# PageMain.net
KiCad netlist of a schematic drawn in Altium Designer
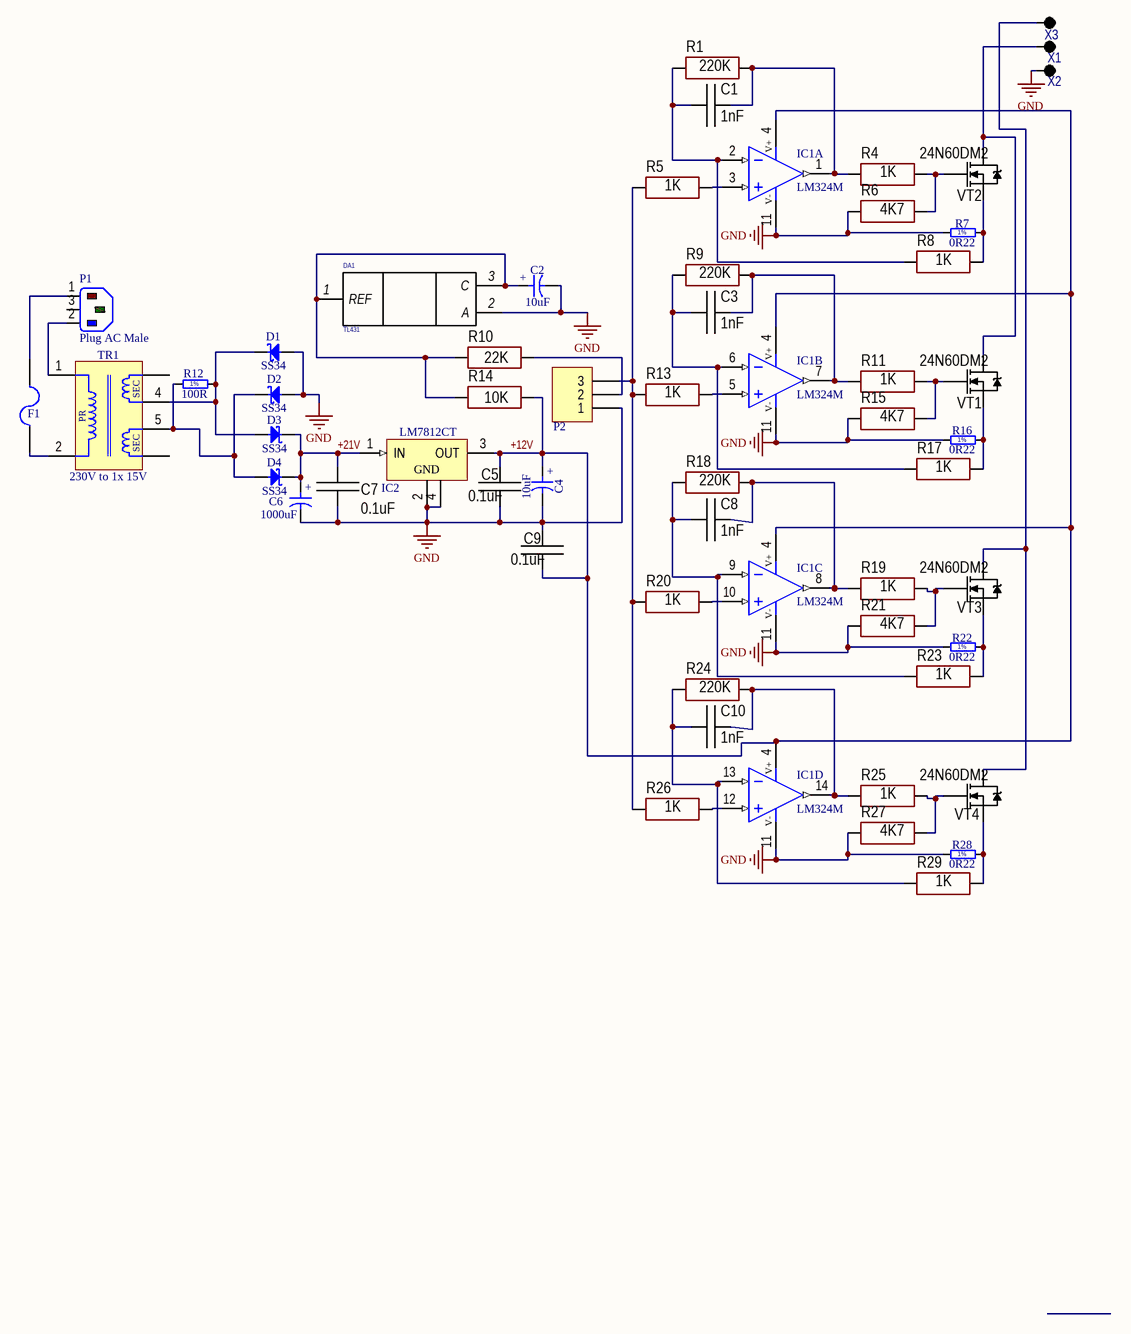
[diagram p0: PageMain.SchDoc]

(export (version "E")
  (design (tool "Eeschema 10.0.6"))
  (components
    (comp (ref "C1")
      (value "1nF")
      (footprint "CAP: 0805")
      (fields
        (field (name "MANUFACTURER") "Yageo")
        (field (name "PARTNUMBER") "CC0805KRX7R7BB104")
        (field (name "VALUEMANUFACTURERPARTNUMBER") "Ceramic capacitor, 1nF, X7R, ±10%, 16V, 0805, -55...+125°C")
      )
      (libsource (lib "Capacitor") (part "Ceramic_0805"))
    )
    (comp (ref "C2")
      (value "10uF")
      (footprint "CAPPR200-500X1100")
      (description "Polarised capacitor")
      (fields
        (field (name "PART NUMBER") "CAER_10UF_63V_20%_PANASONIC_ECA1JM100")
        (field (name "VOLTAGE") "63V")
        (field (name "AUTHOR") "CERN DEM JLC")
      )
      (libsource (lib "Capacitors") (part "Capacitor - polarized"))
    )
    (comp (ref "C3")
      (value "1nF")
      (footprint "CAP: 0805")
      (fields
        (field (name "MANUFACTURER") "Yageo")
        (field (name "PARTNUMBER") "CC0805KRX7R7BB104")
        (field (name "VALUEMANUFACTURERPARTNUMBER") "Ceramic capacitor, 1nF, X7R, ±10%, 16V, 0805, -55...+125°C")
      )
      (libsource (lib "Capacitor") (part "Ceramic_0805"))
    )
    (comp (ref "C4")
      (value "10uF")
      (footprint "CAPPR200-500X1100")
      (description "Polarised capacitor")
      (fields
        (field (name "PART NUMBER") "CAER_10UF_63V_20%_PANASONIC_ECA1JM100")
        (field (name "VOLTAGE") "63V")
        (field (name "AUTHOR") "CERN DEM JLC")
      )
      (libsource (lib "Capacitors") (part "Capacitor - polarized"))
    )
    (comp (ref "C5")
      (value "0.1uF")
      (footprint "CAP: 0805")
      (fields
        (field (name "MANUFACTURER") "Yageo")
        (field (name "PARTNUMBER") "CC0805KRX7R7BB104")
        (field (name "VALUEMANUFACTURERPARTNUMBER") "Ceramic capacitor, 0.1uF, X7R, ±10%, 16V, 0805, -55...+125°C")
      )
      (libsource (lib "Capacitor") (part "Ceramic_0805"))
    )
    (comp (ref "C6")
      (value "1000uF")
      (footprint "CAPPR500-1300X2700")
      (description "Polarised capacitor")
      (fields
        (field (name "PART NUMBER") "CAER_1000UF_35V_20%_VISHAY_MAL215050102E3")
        (field (name "VOLTAGE") "35V")
        (field (name "AUTHOR") "CERN DEM JLC")
      )
      (libsource (lib "Capacitors") (part "Capacitor - polarized"))
    )
    (comp (ref "C7")
      (value "0.1uF")
      (footprint "CAP: 0805")
      (fields
        (field (name "MANUFACTURER") "Yageo")
        (field (name "PARTNUMBER") "CC0805KRX7R7BB104")
        (field (name "VALUEMANUFACTURERPARTNUMBER") "Ceramic capacitor, 0.1uF, X7R, ±10%, 16V, 0805, -55...+125°C")
      )
      (libsource (lib "Capacitor") (part "Ceramic_0805"))
    )
    (comp (ref "C8")
      (value "1nF")
      (footprint "CAP: 0805")
      (fields
        (field (name "MANUFACTURER") "Yageo")
        (field (name "PARTNUMBER") "CC0805KRX7R7BB104")
        (field (name "VALUEMANUFACTURERPARTNUMBER") "Ceramic capacitor, 1nF, X7R, ±10%, 16V, 0805, -55...+125°C")
      )
      (libsource (lib "Capacitor") (part "Ceramic_0805"))
    )
    (comp (ref "C9")
      (value "0.1uF")
      (footprint "CAP: 0805")
      (fields
        (field (name "MANUFACTURER") "Yageo")
        (field (name "PARTNUMBER") "CC0805KRX7R7BB104")
        (field (name "VALUEMANUFACTURERPARTNUMBER") "Ceramic capacitor, 0.1uF, X7R, ±10%, 16V, 0805, -55...+125°C")
      )
      (libsource (lib "Capacitor") (part "Ceramic_0805"))
    )
    (comp (ref "C10")
      (value "1nF")
      (footprint "CAP: 0805")
      (fields
        (field (name "MANUFACTURER") "Yageo")
        (field (name "PARTNUMBER") "CC0805KRX7R7BB104")
        (field (name "VALUEMANUFACTURERPARTNUMBER") "Ceramic capacitor, 1nF, X7R, ±10%, 16V, 0805, -55...+125°C")
      )
      (libsource (lib "Capacitor") (part "Ceramic_0805"))
    )
    (comp (ref "D1")
      (value "SS34")
      (footprint "DIOM7659X265N")
      (description "Schottky Diode")
      (fields
        (field (name "VOLTAGE") "40V")
        (field (name "POWER") "3A")
        (field (name "AUTHOR") "CERN DEM JLC")
      )
      (libsource (lib "ICs And Semiconductors") (part "Diode Schottky"))
    )
    (comp (ref "D2")
      (value "SS34")
      (footprint "DIOM7659X265N")
      (description "Schottky Diode")
      (fields
        (field (name "VOLTAGE") "40V")
        (field (name "POWER") "3A")
        (field (name "AUTHOR") "CERN DEM JLC")
      )
      (libsource (lib "ICs And Semiconductors") (part "Diode Schottky"))
    )
    (comp (ref "D3")
      (value "SS34")
      (footprint "DIOM7659X265N")
      (description "Schottky Diode")
      (fields
        (field (name "VOLTAGE") "40V")
        (field (name "POWER") "3A")
        (field (name "AUTHOR") "CERN DEM JLC")
      )
      (libsource (lib "ICs And Semiconductors") (part "Diode Schottky"))
    )
    (comp (ref "D4")
      (value "SS34")
      (footprint "DIOM7659X265N")
      (description "Schottky Diode")
      (fields
        (field (name "VOLTAGE") "40V")
        (field (name "POWER") "3A")
        (field (name "AUTHOR") "CERN DEM JLC")
      )
      (libsource (lib "ICs And Semiconductors") (part "Diode Schottky"))
    )
    (comp (ref "DA1") (value "TL431") (footprint "TO-92") (libsource (lib "lib") (part "TL431")))
    (comp (ref "F1")
      (value "~")
      (footprint "PIN-W2/E2.8")
      (description "Fuse")
      (fields (field (name "PUBLISHER") "Altium Limited"))
      (libsource (lib "Miscellaneous Devices") (part "Fuse 2"))
    )
    (comp (ref "IC1")
      (value "LM324M")
      (footprint "SOIC127P600X175-14N")
      (description "Quad Operational Amplifier")
      (fields (field (name "MANUFACTURER") "FAIRCHILD SEMICONDUCTOR") (field (name "AUTHOR") "CERN DEM JLC"))
      (libsource (lib "ICs And Semiconductors") (part "Operational Amplifier x4 Type1"))
    )
    (comp (ref "IC2")
      (value "LM7812CT")
      (footprint "TO-220-H")
      (description "3-Terminal Regulator 1=IN 2=GND 3=OUT 4=GND")
      (fields
        (field (name "PART NUMBER") "LM7812CT_h")
        (field (name "MANUFACTURER") "FAIRCHILD SEMICONDUCTOR")
        (field (name "AUTHOR") "CERN DEM JLC")
      )
      (libsource (lib "ICs And Semiconductors") (part "REG3+1 1IN-2GND-3OUT+4GND"))
    )
    (comp (ref "P1")
      (value "Plug AC Male")
      (footprint "IEC9.14-2H3")
      (description "IEC Mains Power Inlet, EN60 320-1 C14 Class I Cold Condition, PC Flange Rear Mount, Chassis Plug")
      (fields (field (name "PUBLISHER") "Altium Limited"))
      (libsource (lib "Miscellaneous Connectors") (part "Plug AC Male"))
    )
    (comp (ref "P2")
      (value "Header 3")
      (footprint "HDR1X3")
      (description "Header, 3-Pin")
      (fields (field (name "PUBLISHER") "Altium Limited"))
      (libsource (lib "Miscellaneous Connectors") (part "Header 3"))
    )
    (comp (ref "R1")
      (value "220K")
      (footprint "RES: 0805")
      (fields
        (field (name "MANUFACTURER") "Yageo")
        (field (name "PARTNUMBER") "RC0805JR-07100RL")
        (field (name "VALUEMANUFACTURERPARTNUMBER") "Resistor film, 220K, ±5%, 0805, 0.125W, -55...+125°C")
      )
      (libsource (lib "") (part "Resistor_0805_1"))
    )
    (comp (ref "R4")
      (value "1K")
      (footprint "RES: 0805")
      (fields
        (field (name "MANUFACTURER") "Yageo")
        (field (name "PARTNUMBER") "RC0805JR-07100RL")
        (field (name "VALUEMANUFACTURERPARTNUMBER") "Resistor film, 1K, ±5%, 0805, 0.125W, -55...+125°C")
      )
      (libsource (lib "Resistor") (part "Resistor_0805"))
    )
    (comp (ref "R5")
      (value "1K")
      (footprint "RES: 0805")
      (fields
        (field (name "MANUFACTURER") "Yageo")
        (field (name "PARTNUMBER") "RC0805JR-07100RL")
        (field (name "VALUEMANUFACTURERPARTNUMBER") "Resistor film, 1K, ±5%, 0805, 0.125W, -55...+125°C")
      )
      (libsource (lib "") (part "Resistor_0805_1"))
    )
    (comp (ref "R6")
      (value "4K7")
      (footprint "RES: 0805")
      (fields
        (field (name "MANUFACTURER") "Yageo")
        (field (name "PARTNUMBER") "RC0805JR-07100RL")
        (field (name "VALUEMANUFACTURERPARTNUMBER") "Resistor film, 4K7, ±5%, 0805, 0.125W, -55...+125°C")
      )
      (libsource (lib "Resistor") (part "Resistor_0805"))
    )
    (comp (ref "R7")
      (value "0R22")
      (footprint "RES_OHMITE_45")
      (description "Resistor")
      (fields (field (name "POWER") "5W") (field (name "AUTHOR") "CERN DEM MR"))
      (libsource (lib "Resistors") (part "Resistor - 1%"))
    )
    (comp (ref "R8")
      (value "1K")
      (footprint "RES: 0805")
      (fields
        (field (name "MANUFACTURER") "Yageo")
        (field (name "PARTNUMBER") "RC0805JR-07100RL")
        (field (name "VALUEMANUFACTURERPARTNUMBER") "Resistor film, 1K, ±5%, 0805, 0.125W, -55...+125°C")
      )
      (libsource (lib "") (part "Resistor_0805_1"))
    )
    (comp (ref "R9")
      (value "220K")
      (footprint "RES: 0805")
      (fields
        (field (name "MANUFACTURER") "Yageo")
        (field (name "PARTNUMBER") "RC0805JR-07100RL")
        (field (name "VALUEMANUFACTURERPARTNUMBER") "Resistor film, 220K, ±5%, 0805, 0.125W, -55...+125°C")
      )
      (libsource (lib "") (part "Resistor_0805_1"))
    )
    (comp (ref "R10")
      (value "22K")
      (footprint "RES: 0805")
      (fields
        (field (name "MANUFACTURER") "Yageo")
        (field (name "PARTNUMBER") "RC0805JR-07100RL")
        (field (name "VALUEMANUFACTURERPARTNUMBER") "Resistor film, 22K, ±5%, 0805, 0.125W, -55...+125°C")
      )
      (libsource (lib "") (part "Resistor_0805_2"))
    )
    (comp (ref "R11")
      (value "1K")
      (footprint "RES: 0805")
      (fields
        (field (name "MANUFACTURER") "Yageo")
        (field (name "PARTNUMBER") "RC0805JR-07100RL")
        (field (name "VALUEMANUFACTURERPARTNUMBER") "Resistor film, 1K, ±5%, 0805, 0.125W, -55...+125°C")
      )
      (libsource (lib "Resistor") (part "Resistor_0805"))
    )
    (comp (ref "R12")
      (value "100R")
      (footprint "RES_OHMITE_45")
      (description "Resistor")
      (fields (field (name "POWER") "5W") (field (name "AUTHOR") "CERN DEM MR"))
      (libsource (lib "Resistors") (part "Resistor - 1%"))
    )
    (comp (ref "R13")
      (value "1K")
      (footprint "RES: 0805")
      (fields
        (field (name "MANUFACTURER") "Yageo")
        (field (name "PARTNUMBER") "RC0805JR-07100RL")
        (field (name "VALUEMANUFACTURERPARTNUMBER") "Resistor film, 1K, ±5%, 0805, 0.125W, -55...+125°C")
      )
      (libsource (lib "") (part "Resistor_0805_1"))
    )
    (comp (ref "R14")
      (value "10K")
      (footprint "RES: 0805")
      (fields
        (field (name "MANUFACTURER") "Yageo")
        (field (name "PARTNUMBER") "RC0805JR-07100RL")
        (field (name "VALUEMANUFACTURERPARTNUMBER") "Resistor film, 10K, ±5%, 0805, 0.125W, -55...+125°C")
      )
      (libsource (lib "") (part "Resistor_0805_2"))
    )
    (comp (ref "R15")
      (value "4K7")
      (footprint "RES: 0805")
      (fields
        (field (name "MANUFACTURER") "Yageo")
        (field (name "PARTNUMBER") "RC0805JR-07100RL")
        (field (name "VALUEMANUFACTURERPARTNUMBER") "Resistor film, 4K7, ±5%, 0805, 0.125W, -55...+125°C")
      )
      (libsource (lib "Resistor") (part "Resistor_0805"))
    )
    (comp (ref "R16")
      (value "0R22")
      (footprint "RES_OHMITE_45")
      (description "Resistor")
      (fields (field (name "POWER") "5W") (field (name "AUTHOR") "CERN DEM MR"))
      (libsource (lib "Resistors") (part "Resistor - 1%"))
    )
    (comp (ref "R17")
      (value "1K")
      (footprint "RES: 0805")
      (fields
        (field (name "MANUFACTURER") "Yageo")
        (field (name "PARTNUMBER") "RC0805JR-07100RL")
        (field (name "VALUEMANUFACTURERPARTNUMBER") "Resistor film, 1K, ±5%, 0805, 0.125W, -55...+125°C")
      )
      (libsource (lib "") (part "Resistor_0805_1"))
    )
    (comp (ref "R18")
      (value "220K")
      (footprint "RES: 0805")
      (fields
        (field (name "MANUFACTURER") "Yageo")
        (field (name "PARTNUMBER") "RC0805JR-07100RL")
        (field (name "VALUEMANUFACTURERPARTNUMBER") "Resistor film, 220K, ±5%, 0805, 0.125W, -55...+125°C")
      )
      (libsource (lib "") (part "Resistor_0805_1"))
    )
    (comp (ref "R19")
      (value "1K")
      (footprint "RES: 0805")
      (fields
        (field (name "MANUFACTURER") "Yageo")
        (field (name "PARTNUMBER") "RC0805JR-07100RL")
        (field (name "VALUEMANUFACTURERPARTNUMBER") "Resistor film, 1K, ±5%, 0805, 0.125W, -55...+125°C")
      )
      (libsource (lib "Resistor") (part "Resistor_0805"))
    )
    (comp (ref "R20")
      (value "1K")
      (footprint "RES: 0805")
      (fields
        (field (name "MANUFACTURER") "Yageo")
        (field (name "PARTNUMBER") "RC0805JR-07100RL")
        (field (name "VALUEMANUFACTURERPARTNUMBER") "Resistor film, 1K, ±5%, 0805, 0.125W, -55...+125°C")
      )
      (libsource (lib "") (part "Resistor_0805_1"))
    )
    (comp (ref "R21")
      (value "4K7")
      (footprint "RES: 0805")
      (fields
        (field (name "MANUFACTURER") "Yageo")
        (field (name "PARTNUMBER") "RC0805JR-07100RL")
        (field (name "VALUEMANUFACTURERPARTNUMBER") "Resistor film, 4K7, ±5%, 0805, 0.125W, -55...+125°C")
      )
      (libsource (lib "Resistor") (part "Resistor_0805"))
    )
    (comp (ref "R22")
      (value "0R22")
      (footprint "RES_OHMITE_45")
      (description "Resistor")
      (fields (field (name "POWER") "5W") (field (name "AUTHOR") "CERN DEM MR"))
      (libsource (lib "Resistors") (part "Resistor - 1%"))
    )
    (comp (ref "R23")
      (value "1K")
      (footprint "RES: 0805")
      (fields
        (field (name "MANUFACTURER") "Yageo")
        (field (name "PARTNUMBER") "RC0805JR-07100RL")
        (field (name "VALUEMANUFACTURERPARTNUMBER") "Resistor film, 1K, ±5%, 0805, 0.125W, -55...+125°C")
      )
      (libsource (lib "") (part "Resistor_0805_1"))
    )
    (comp (ref "R24")
      (value "220K")
      (footprint "RES: 0805")
      (fields
        (field (name "MANUFACTURER") "Yageo")
        (field (name "PARTNUMBER") "RC0805JR-07100RL")
        (field (name "VALUEMANUFACTURERPARTNUMBER") "Resistor film, 220K, ±5%, 0805, 0.125W, -55...+125°C")
      )
      (libsource (lib "") (part "Resistor_0805_1"))
    )
    (comp (ref "R25")
      (value "1K")
      (footprint "RES: 0805")
      (fields
        (field (name "MANUFACTURER") "Yageo")
        (field (name "PARTNUMBER") "RC0805JR-07100RL")
        (field (name "VALUEMANUFACTURERPARTNUMBER") "Resistor film, 1K, ±5%, 0805, 0.125W, -55...+125°C")
      )
      (libsource (lib "Resistor") (part "Resistor_0805"))
    )
    (comp (ref "R26")
      (value "1K")
      (footprint "RES: 0805")
      (fields
        (field (name "MANUFACTURER") "Yageo")
        (field (name "PARTNUMBER") "RC0805JR-07100RL")
        (field (name "VALUEMANUFACTURERPARTNUMBER") "Resistor film, 1K, ±5%, 0805, 0.125W, -55...+125°C")
      )
      (libsource (lib "") (part "Resistor_0805_1"))
    )
    (comp (ref "R27")
      (value "4K7")
      (footprint "RES: 0805")
      (fields
        (field (name "MANUFACTURER") "Yageo")
        (field (name "PARTNUMBER") "RC0805JR-07100RL")
        (field (name "VALUEMANUFACTURERPARTNUMBER") "Resistor film, 4K7, ±5%, 0805, 0.125W, -55...+125°C")
      )
      (libsource (lib "Resistor") (part "Resistor_0805"))
    )
    (comp (ref "R28")
      (value "0R22")
      (footprint "RES_OHMITE_45")
      (description "Resistor")
      (fields (field (name "POWER") "5W") (field (name "AUTHOR") "CERN DEM MR"))
      (libsource (lib "Resistors") (part "Resistor - 1%"))
    )
    (comp (ref "R29")
      (value "1K")
      (footprint "RES: 0805")
      (fields
        (field (name "MANUFACTURER") "Yageo")
        (field (name "PARTNUMBER") "RC0805JR-07100RL")
        (field (name "VALUEMANUFACTURERPARTNUMBER") "Resistor film, 1K, ±5%, 0805, 0.125W, -55...+125°C")
      )
      (libsource (lib "") (part "Resistor_0805_1"))
    )
    (comp (ref "TR1")
      (value "230V to 1x 15V")
      (footprint "XFMR_CLAIRTRONIC_14102")
      (description "Transformer 1xPrim 1xSec Type1")
      (fields
        (field (name "PART NUMBER") "XFMR_CLAIRTRONIC_14102")
        (field (name "MANUFACTURER") "CLAIRTRONIC LTD")
        (field (name "AUTHOR") "CERN DEM JMW")
      )
      (libsource (lib "Inductors & Transformers") (part "Transformer 1xPrim 2xSec Type1"))
    )
    (comp (ref "VT1")
      (value "~")
      (footprint "TO247")
      (fields
        (field (name "MANUFACTURER") "Infineon Technologies")
        (field (name "VALUEMANUFACTURERPARTNUMBER") "MOSFET N-channel transistor, 80V, 7A, 9.1nC, 2.5W, 34mOhm, 756pF, 8-TDSON, -55...+150°C")
        (field (name "PARTNUMBER") "24N60DM2")
      )
      (libsource (lib "Transistor") (part "MOSFET_N_123"))
    )
    (comp (ref "VT2")
      (value "~")
      (footprint "TO247")
      (fields
        (field (name "MANUFACTURER") "Infineon Technologies")
        (field (name "VALUEMANUFACTURERPARTNUMBER") "MOSFET N-channel transistor, 80V, 7A, 9.1nC, 2.5W, 34mOhm, 756pF, 8-TDSON, -55...+150°C")
        (field (name "PARTNUMBER") "24N60DM2")
      )
      (libsource (lib "Transistor") (part "MOSFET_N_123"))
    )
    (comp (ref "VT3")
      (value "~")
      (footprint "TO247")
      (fields
        (field (name "MANUFACTURER") "Infineon Technologies")
        (field (name "VALUEMANUFACTURERPARTNUMBER") "MOSFET N-channel transistor, 80V, 7A, 9.1nC, 2.5W, 34mOhm, 756pF, 8-TDSON, -55...+150°C")
        (field (name "PARTNUMBER") "24N60DM2")
      )
      (libsource (lib "Transistor") (part "MOSFET_N_123"))
    )
    (comp (ref "VT4")
      (value "~")
      (footprint "TO247")
      (fields
        (field (name "MANUFACTURER") "Infineon Technologies")
        (field (name "VALUEMANUFACTURERPARTNUMBER") "MOSFET N-channel transistor, 80V, 7A, 9.1nC, 2.5W, 34mOhm, 756pF, 8-TDSON, -55...+150°C")
        (field (name "PARTNUMBER") "24N60DM2")
      )
      (libsource (lib "Transistor") (part "MOSFET_N_123"))
    )
    (comp (ref "X1")
      (value "62650-1")
      (footprint "62650-1")
      (description "Ножевой контакт 6,3мм на плату")
      (fields (field (name "MANUFACTURER") "TE Connectivity"))
      (libsource (lib "lib") (part "POINT"))
    )
    (comp (ref "X2")
      (value "62650-1")
      (footprint "62650-1")
      (description "Ножевой контакт 6,3мм на плату")
      (fields (field (name "MANUFACTURER") "TE Connectivity"))
      (libsource (lib "lib") (part "POINT"))
    )
    (comp (ref "X3")
      (value "62650-1")
      (footprint "62650-1")
      (description "Ножевой контакт 6,3мм на плату")
      (fields (field (name "MANUFACTURER") "TE Connectivity"))
      (libsource (lib "lib") (part "POINT"))
    )
  )
  (nets
    (net (code "1") (name "/+12V") (class "Default")
      (node (ref "C4") (pin "1") (pinfunction "1_1") (pintype "passive"))
      (node (ref "C5") (pin "1") (pinfunction "1_1") (pintype "power_in"))
      (node (ref "C9") (pin "2") (pinfunction "2_2") (pintype "power_in"))
      (node (ref "IC1") (pin "4") (pinfunction "V+_4") (pintype "power_in"))
      (node (ref "IC2") (pin "3") (pinfunction "OUT_3") (pintype "power_in"))
      (node (ref "R14") (pin "1") (pinfunction "1_1") (pintype "passive"))
    )
    (net (code "2") (name "/+21V") (class "Default")
      (node (ref "C6") (pin "1") (pinfunction "1_1") (pintype "passive"))
      (node (ref "C7") (pin "1") (pinfunction "1_1") (pintype "power_in"))
      (node (ref "D3") (pin "1") (pinfunction "C_1") (pintype "passive"))
      (node (ref "D4") (pin "1") (pinfunction "C_1") (pintype "passive"))
      (node (ref "IC2") (pin "1") (pinfunction "IN_1") (pintype "input"))
    )
    (net (code "3") (name "GND") (class "Default")
      (node (ref "C2") (pin "2") (pinfunction "2_2") (pintype "passive"))
      (node (ref "C4") (pin "2") (pinfunction "2_2") (pintype "passive"))
      (node (ref "C5") (pin "2") (pinfunction "2_2") (pintype "power_in"))
      (node (ref "C6") (pin "2") (pinfunction "2_2") (pintype "passive"))
      (node (ref "C7") (pin "2") (pinfunction "2_2") (pintype "power_in"))
      (node (ref "C9") (pin "1") (pinfunction "1_1") (pintype "power_in"))
      (node (ref "D1") (pin "2") (pinfunction "A_2") (pintype "passive"))
      (node (ref "D2") (pin "2") (pinfunction "A_2") (pintype "passive"))
      (node (ref "DA1") (pin "2") (pinfunction "A_2") (pintype "passive"))
      (node (ref "IC1") (pin "11") (pinfunction "V-_11") (pintype "power_in"))
      (node (ref "IC2") (pin "2") (pinfunction "GND_2") (pintype "power_in"))
      (node (ref "IC2") (pin "4") (pinfunction "GND_4") (pintype "power_in"))
      (node (ref "P2") (pin "1") (pinfunction "1_1") (pintype "passive"))
      (node (ref "R15") (pin "1") (pinfunction "1_1") (pintype "passive"))
      (node (ref "R16") (pin "1") (pinfunction "1_1") (pintype "passive"))
      (node (ref "R21") (pin "1") (pinfunction "1_1") (pintype "passive"))
      (node (ref "R22") (pin "1") (pinfunction "1_1") (pintype "passive"))
      (node (ref "R27") (pin "1") (pinfunction "1_1") (pintype "passive"))
      (node (ref "R28") (pin "1") (pinfunction "1_1") (pintype "passive"))
      (node (ref "R6") (pin "1") (pinfunction "1_1") (pintype "passive"))
      (node (ref "R7") (pin "1") (pinfunction "1_1") (pintype "passive"))
      (node (ref "X2") (pin "1") (pinfunction "1_1") (pintype "passive"))
    )
    (net (code "4") (name "Net-(D1-C)") (class "Default")
      (node (ref "D1") (pin "1") (pinfunction "C_1") (pintype "passive"))
      (node (ref "D3") (pin "2") (pinfunction "A_2") (pintype "passive"))
      (node (ref "R12") (pin "2") (pinfunction "2_2") (pintype "passive"))
      (node (ref "TR1") (pin "4") (pinfunction "4_4") (pintype "passive"))
    )
    (net (code "5") (name "Net-(D2-C)") (class "Default")
      (node (ref "D2") (pin "1") (pinfunction "C_1") (pintype "passive"))
      (node (ref "D4") (pin "2") (pinfunction "A_2") (pintype "passive"))
      (node (ref "R12") (pin "1") (pinfunction "1_1") (pintype "passive"))
      (node (ref "TR1") (pin "5") (pinfunction "5_5") (pintype "passive"))
    )
    (net (code "6") (name "Net-(DA1-C)") (class "Default")
      (node (ref "C2") (pin "1") (pinfunction "1_1") (pintype "passive"))
      (node (ref "DA1") (pin "1") (pinfunction "REF_1") (pintype "passive"))
      (node (ref "DA1") (pin "3") (pinfunction "C_3") (pintype "passive"))
      (node (ref "R10") (pin "2") (pinfunction "2_2") (pintype "passive"))
      (node (ref "R14") (pin "2") (pinfunction "2_2") (pintype "passive"))
    )
    (net (code "7") (name "Net-(F1-Pad1)") (class "Default")
      (node (ref "F1") (pin "1") (pinfunction "1_1") (pintype "passive"))
      (node (ref "TR1") (pin "2") (pinfunction "2_2") (pintype "passive"))
    )
    (net (code "8") (name "Net-(IC1A-IN+)") (class "Default")
      (node (ref "IC1") (pin "3") (pinfunction "IN+_3") (pintype "input"))
      (node (ref "R5") (pin "2") (pinfunction "2_2") (pintype "passive"))
    )
    (net (code "9") (name "Net-(IC1A-IN-)") (class "Default")
      (node (ref "C1") (pin "2") (pinfunction "2_2") (pintype "power_in"))
      (node (ref "IC1") (pin "2") (pinfunction "IN-_2") (pintype "input"))
      (node (ref "R1") (pin "1") (pinfunction "1_1") (pintype "passive"))
      (node (ref "R8") (pin "1") (pinfunction "1_1") (pintype "passive"))
    )
    (net (code "10") (name "Net-(IC1A-OUT)") (class "Default")
      (node (ref "C1") (pin "1") (pinfunction "1_1") (pintype "power_in"))
      (node (ref "IC1") (pin "1") (pinfunction "OUT_1") (pintype "output"))
      (node (ref "R1") (pin "2") (pinfunction "2_2") (pintype "passive"))
      (node (ref "R4") (pin "1") (pinfunction "1_1") (pintype "passive"))
    )
    (net (code "11") (name "Net-(IC1B-IN+)") (class "Default")
      (node (ref "IC1") (pin "5") (pinfunction "IN+_5") (pintype "input"))
      (node (ref "R13") (pin "2") (pinfunction "2_2") (pintype "passive"))
    )
    (net (code "12") (name "Net-(IC1B-IN-)") (class "Default")
      (node (ref "C3") (pin "2") (pinfunction "2_2") (pintype "power_in"))
      (node (ref "IC1") (pin "6") (pinfunction "IN-_6") (pintype "input"))
      (node (ref "R17") (pin "1") (pinfunction "1_1") (pintype "passive"))
      (node (ref "R9") (pin "1") (pinfunction "1_1") (pintype "passive"))
    )
    (net (code "13") (name "Net-(IC1B-OUT)") (class "Default")
      (node (ref "C3") (pin "1") (pinfunction "1_1") (pintype "power_in"))
      (node (ref "IC1") (pin "7") (pinfunction "OUT_7") (pintype "output"))
      (node (ref "R11") (pin "1") (pinfunction "1_1") (pintype "passive"))
      (node (ref "R9") (pin "2") (pinfunction "2_2") (pintype "passive"))
    )
    (net (code "14") (name "Net-(IC1C-IN+)") (class "Default")
      (node (ref "IC1") (pin "10") (pinfunction "IN+_10") (pintype "input"))
      (node (ref "R20") (pin "2") (pinfunction "2_2") (pintype "passive"))
    )
    (net (code "15") (name "Net-(IC1C-IN-)") (class "Default")
      (node (ref "C8") (pin "2") (pinfunction "2_2") (pintype "power_in"))
      (node (ref "IC1") (pin "9") (pinfunction "IN-_9") (pintype "input"))
      (node (ref "R18") (pin "1") (pinfunction "1_1") (pintype "passive"))
      (node (ref "R23") (pin "1") (pinfunction "1_1") (pintype "passive"))
    )
    (net (code "16") (name "Net-(IC1C-OUT)") (class "Default")
      (node (ref "C8") (pin "1") (pinfunction "1_1") (pintype "power_in"))
      (node (ref "IC1") (pin "8") (pinfunction "OUT_8") (pintype "output"))
      (node (ref "R18") (pin "2") (pinfunction "2_2") (pintype "passive"))
      (node (ref "R19") (pin "1") (pinfunction "1_1") (pintype "passive"))
    )
    (net (code "17") (name "Net-(IC1D-IN+)") (class "Default")
      (node (ref "IC1") (pin "12") (pinfunction "IN+_12") (pintype "input"))
      (node (ref "R26") (pin "2") (pinfunction "2_2") (pintype "passive"))
    )
    (net (code "18") (name "Net-(IC1D-IN-)") (class "Default")
      (node (ref "C10") (pin "2") (pinfunction "2_2") (pintype "power_in"))
      (node (ref "IC1") (pin "13") (pinfunction "IN-_13") (pintype "input"))
      (node (ref "R24") (pin "1") (pinfunction "1_1") (pintype "passive"))
      (node (ref "R29") (pin "1") (pinfunction "1_1") (pintype "passive"))
    )
    (net (code "19") (name "Net-(IC1D-OUT)") (class "Default")
      (node (ref "C10") (pin "1") (pinfunction "1_1") (pintype "power_in"))
      (node (ref "IC1") (pin "14") (pinfunction "OUT_14") (pintype "output"))
      (node (ref "R24") (pin "2") (pinfunction "2_2") (pintype "passive"))
      (node (ref "R25") (pin "1") (pinfunction "1_1") (pintype "passive"))
    )
    (net (code "20") (name "Net-(P1-L)") (class "Default")
      (node (ref "F1") (pin "2") (pinfunction "2_2") (pintype "passive"))
      (node (ref "P1") (pin "1") (pinfunction "L_1") (pintype "power_in"))
    )
    (net (code "21") (name "Net-(P1-N)") (class "Default")
      (node (ref "P1") (pin "2") (pinfunction "N_2") (pintype "power_in"))
      (node (ref "TR1") (pin "1") (pinfunction "1_1") (pintype "passive"))
    )
    (net (code "22") (name "Net-(P2-Pad2)") (class "Default")
      (node (ref "P2") (pin "2") (pinfunction "2_2") (pintype "passive"))
      (node (ref "R10") (pin "1") (pinfunction "1_1") (pintype "passive"))
    )
    (net (code "23") (name "Net-(P2-Pad3)") (class "Default")
      (node (ref "P2") (pin "3") (pinfunction "3_3") (pintype "passive"))
      (node (ref "R13") (pin "1") (pinfunction "1_1") (pintype "passive"))
      (node (ref "R20") (pin "1") (pinfunction "1_1") (pintype "passive"))
      (node (ref "R26") (pin "1") (pinfunction "1_1") (pintype "passive"))
      (node (ref "R5") (pin "1") (pinfunction "1_1") (pintype "passive"))
    )
    (net (code "24") (name "Net-(VT1-D)") (class "Default")
      (node (ref "VT1") (pin "2") (pinfunction "D_2") (pintype "passive"))
      (node (ref "VT2") (pin "2") (pinfunction "D_2") (pintype "passive"))
      (node (ref "X1") (pin "1") (pinfunction "1_1") (pintype "passive"))
    )
    (net (code "25") (name "Net-(VT1-G)") (class "Default")
      (node (ref "R11") (pin "2") (pinfunction "2_2") (pintype "passive"))
      (node (ref "R15") (pin "2") (pinfunction "2_2") (pintype "passive"))
      (node (ref "VT1") (pin "1") (pinfunction "G_1") (pintype "passive"))
    )
    (net (code "26") (name "Net-(VT1-S)") (class "Default")
      (node (ref "R16") (pin "2") (pinfunction "2_2") (pintype "passive"))
      (node (ref "R17") (pin "2") (pinfunction "2_2") (pintype "passive"))
      (node (ref "VT1") (pin "3") (pinfunction "S_3") (pintype "passive"))
    )
    (net (code "27") (name "Net-(VT2-G)") (class "Default")
      (node (ref "R4") (pin "2") (pinfunction "2_2") (pintype "passive"))
      (node (ref "R6") (pin "2") (pinfunction "2_2") (pintype "passive"))
      (node (ref "VT2") (pin "1") (pinfunction "G_1") (pintype "passive"))
    )
    (net (code "28") (name "Net-(VT2-S)") (class "Default")
      (node (ref "R7") (pin "2") (pinfunction "2_2") (pintype "passive"))
      (node (ref "R8") (pin "2") (pinfunction "2_2") (pintype "passive"))
      (node (ref "VT2") (pin "3") (pinfunction "S_3") (pintype "passive"))
    )
    (net (code "29") (name "Net-(VT3-D)") (class "Default")
      (node (ref "VT3") (pin "2") (pinfunction "D_2") (pintype "passive"))
      (node (ref "VT4") (pin "2") (pinfunction "D_2") (pintype "passive"))
      (node (ref "X3") (pin "1") (pinfunction "1_1") (pintype "passive"))
    )
    (net (code "30") (name "Net-(VT3-G)") (class "Default")
      (node (ref "R19") (pin "2") (pinfunction "2_2") (pintype "passive"))
      (node (ref "R21") (pin "2") (pinfunction "2_2") (pintype "passive"))
      (node (ref "VT3") (pin "1") (pinfunction "G_1") (pintype "passive"))
    )
    (net (code "31") (name "Net-(VT3-S)") (class "Default")
      (node (ref "R22") (pin "2") (pinfunction "2_2") (pintype "passive"))
      (node (ref "R23") (pin "2") (pinfunction "2_2") (pintype "passive"))
      (node (ref "VT3") (pin "3") (pinfunction "S_3") (pintype "passive"))
    )
    (net (code "32") (name "Net-(VT4-G)") (class "Default")
      (node (ref "R25") (pin "2") (pinfunction "2_2") (pintype "passive"))
      (node (ref "R27") (pin "2") (pinfunction "2_2") (pintype "passive"))
      (node (ref "VT4") (pin "1") (pinfunction "G_1") (pintype "passive"))
    )
    (net (code "33") (name "Net-(VT4-S)") (class "Default")
      (node (ref "R28") (pin "2") (pinfunction "2_2") (pintype "passive"))
      (node (ref "R29") (pin "2") (pinfunction "2_2") (pintype "passive"))
      (node (ref "VT4") (pin "3") (pinfunction "S_3") (pintype "passive"))
    )
    (net (code "34") (name "unconnected-(P1-E-Pad3)") (class "Default")
      (node (ref "P1") (pin "3") (pinfunction "E_3") (pintype "power_in"))
    )
    (net (code "35") (name "unconnected-(TR1-Pad3)") (class "Default")
      (node (ref "TR1") (pin "3") (pinfunction "3_3") (pintype "passive"))
    )
    (net (code "36") (name "unconnected-(TR1-Pad6)") (class "Default")
      (node (ref "TR1") (pin "6") (pinfunction "6_6") (pintype "passive"))
    )
  )
)
